# Controller.net
KiCad netlist of a schematic drawn in EAGLE
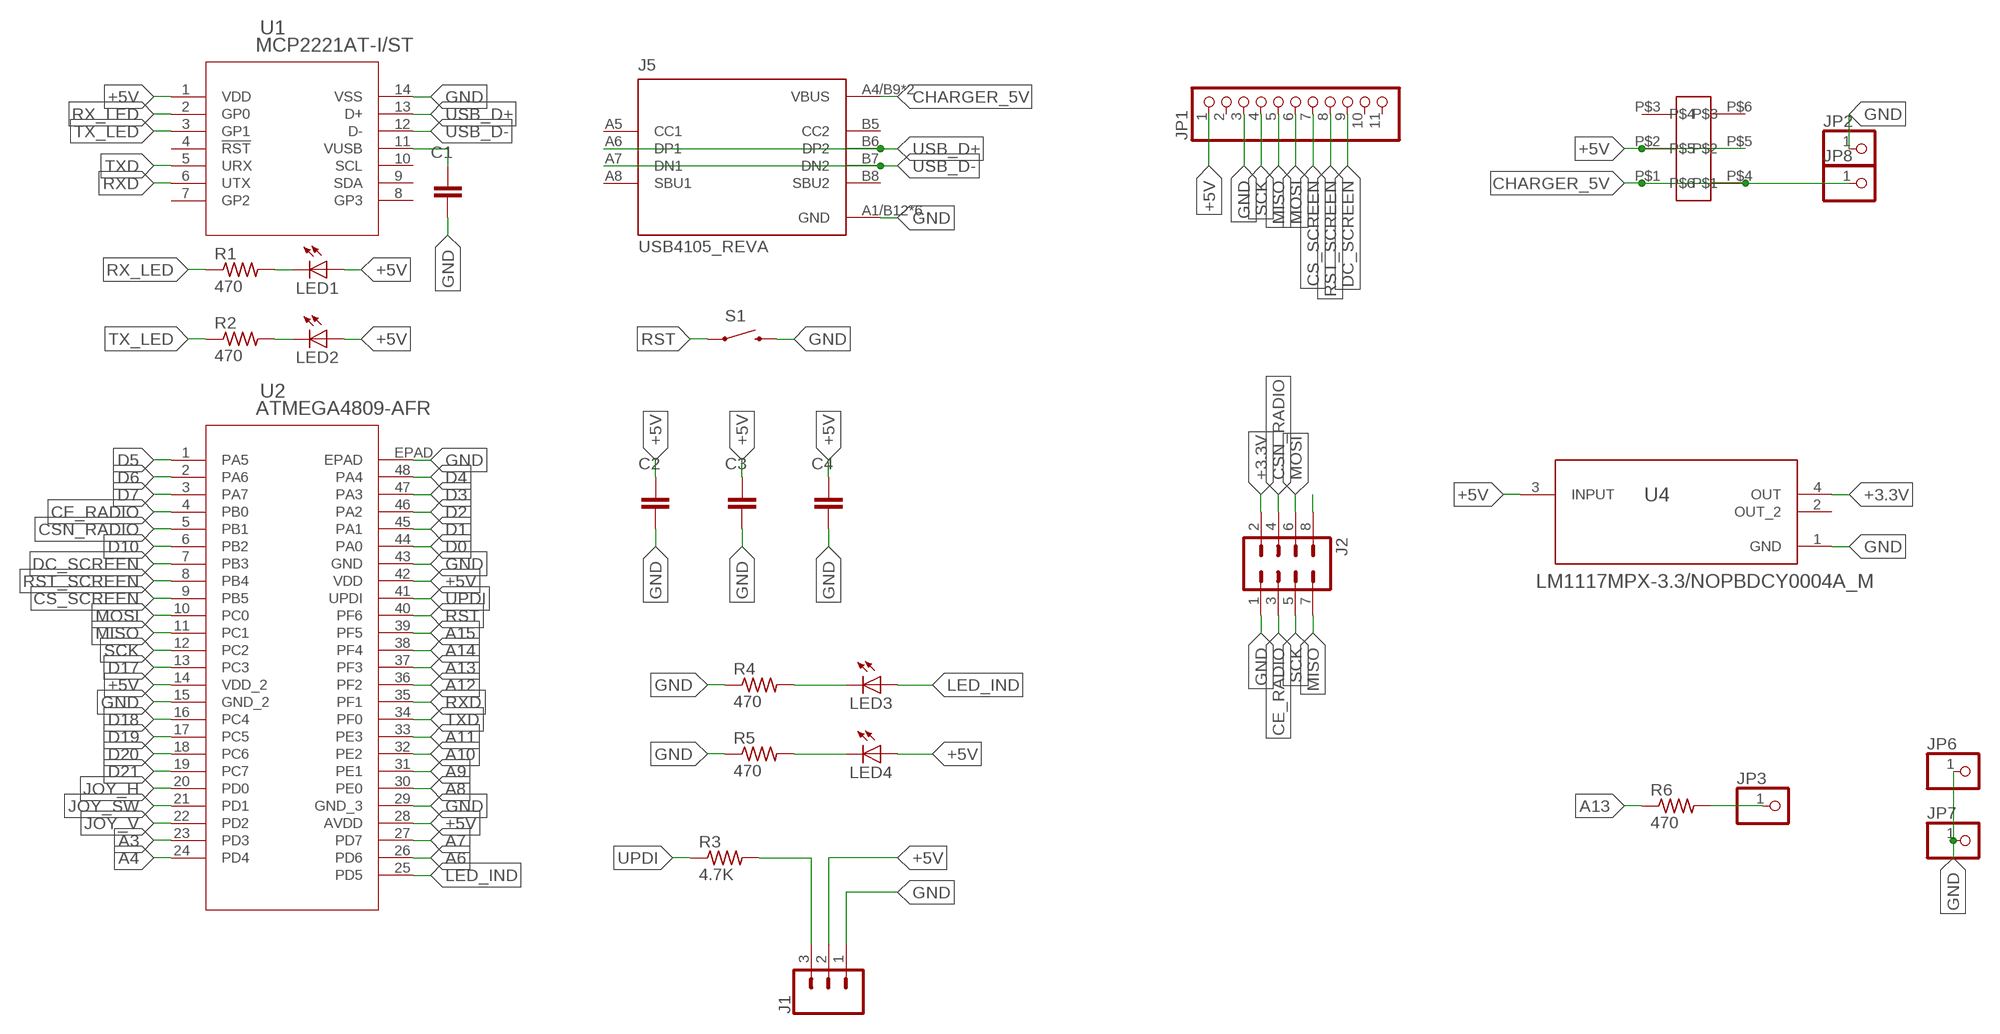
[diagram p0: schematic, sheet 1]

(export (version "E")
  (design (tool "Eeschema 10.0.6"))
  (components
    (comp (ref "C1")
      (value "0.22uF")
      (footprint "eagle-import:CAP_0805")
      (fields
        (field (name "DIGIKEY_PART_NUMBER") "311-1140-2-ND")
        (field (name "MANUFACTURER") "Yageo")
        (field (name "MPN") "CC0805KRX7R9BB104")
        (field (name "CREATED_BY") "PCBLayout.com")
      )
      (libsource (lib "eagle-import") (part "CC0805KRX7R9BB104"))
    )
    (comp (ref "C2")
      (value "0.1uF")
      (footprint "eagle-import:CAP_0805")
      (fields
        (field (name "DIGIKEY_PART_NUMBER") "311-1140-2-ND")
        (field (name "MANUFACTURER") "Yageo")
        (field (name "MPN") "CC0805KRX7R9BB104")
        (field (name "CREATED_BY") "PCBLayout.com")
      )
      (libsource (lib "eagle-import") (part "CC0805KRX7R9BB104"))
    )
    (comp (ref "C3")
      (value "0.1uF")
      (footprint "eagle-import:CAP_0805")
      (fields
        (field (name "DIGIKEY_PART_NUMBER") "311-1140-2-ND")
        (field (name "MANUFACTURER") "Yageo")
        (field (name "MPN") "CC0805KRX7R9BB104")
        (field (name "CREATED_BY") "PCBLayout.com")
      )
      (libsource (lib "eagle-import") (part "CC0805KRX7R9BB104"))
    )
    (comp (ref "C4")
      (value "0.1uF")
      (footprint "eagle-import:CAP_0805")
      (fields
        (field (name "DIGIKEY_PART_NUMBER") "311-1140-2-ND")
        (field (name "MANUFACTURER") "Yageo")
        (field (name "MPN") "CC0805KRX7R9BB104")
        (field (name "CREATED_BY") "PCBLayout.com")
      )
      (libsource (lib "eagle-import") (part "CC0805KRX7R9BB104"))
    )
    (comp (ref "J1")
      (value "CONN_03SMD_RA_MALE")
      (footprint "eagle-import:1X03_SMD_RA_MALE")
      (libsource (lib "eagle-import") (part "CONN_03SMD_RA_MALE"))
    )
    (comp (ref "J2")
      (value "MA04-2")
      (footprint "eagle-import:MA04-2")
      (libsource (lib "eagle-import") (part "MA04-2"))
    )
    (comp (ref "J5")
      (value "USB4105_REVA")
      (footprint "eagle-import:GCT_USB4105_REVA")
      (fields (field (name "MF") "Global Connector Technology") (field (name "MP") "USB4105"))
      (libsource (lib "eagle-import") (part "USB4105_REVA"))
    )
    (comp (ref "JP1")
      (value "PINHD-1X11")
      (footprint "eagle-import:1X11")
      (libsource (lib "eagle-import") (part "PINHD-1X11"))
    )
    (comp (ref "JP2")
      (value "PINHD-1X1")
      (footprint "eagle-import:1X01")
      (libsource (lib "eagle-import") (part "PINHD-1X1"))
    )
    (comp (ref "JP3")
      (value "PINHD-1X1")
      (footprint "eagle-import:1X01")
      (libsource (lib "eagle-import") (part "PINHD-1X1"))
    )
    (comp (ref "JP6")
      (value "PINHD-1X1")
      (footprint "eagle-import:1X01")
      (libsource (lib "eagle-import") (part "PINHD-1X1"))
    )
    (comp (ref "JP7")
      (value "PINHD-1X1")
      (footprint "eagle-import:1X01")
      (libsource (lib "eagle-import") (part "PINHD-1X1"))
    )
    (comp (ref "JP8")
      (value "PINHD-1X1")
      (footprint "eagle-import:1X01")
      (libsource (lib "eagle-import") (part "PINHD-1X1"))
    )
    (comp (ref "LED1")
      (value "LEDCHIPLED_0805")
      (footprint "eagle-import:CHIPLED_0805")
      (libsource (lib "eagle-import") (part "LEDCHIPLED_0805"))
    )
    (comp (ref "LED2")
      (value "LEDCHIPLED_0805")
      (footprint "eagle-import:CHIPLED_0805")
      (libsource (lib "eagle-import") (part "LEDCHIPLED_0805"))
    )
    (comp (ref "LED3")
      (value "LEDCHIPLED_0805")
      (footprint "eagle-import:CHIPLED_0805")
      (libsource (lib "eagle-import") (part "LEDCHIPLED_0805"))
    )
    (comp (ref "LED4")
      (value "LEDCHIPLED_0805")
      (footprint "eagle-import:CHIPLED_0805")
      (libsource (lib "eagle-import") (part "LEDCHIPLED_0805"))
    )
    (comp (ref "R1")
      (value "470")
      (footprint "eagle-import:R0805")
      (libsource (lib "eagle-import") (part "R-US_R0805"))
    )
    (comp (ref "R2")
      (value "470")
      (footprint "eagle-import:R0805")
      (libsource (lib "eagle-import") (part "R-US_R0805"))
    )
    (comp (ref "R3")
      (value "4.7K")
      (footprint "eagle-import:R0805")
      (libsource (lib "eagle-import") (part "R-US_R0805"))
    )
    (comp (ref "R4")
      (value "470")
      (footprint "eagle-import:R0805")
      (libsource (lib "eagle-import") (part "R-US_R0805"))
    )
    (comp (ref "R5")
      (value "470")
      (footprint "eagle-import:R0805")
      (libsource (lib "eagle-import") (part "R-US_R0805"))
    )
    (comp (ref "R6")
      (value "470")
      (footprint "eagle-import:R0805")
      (libsource (lib "eagle-import") (part "R-US_R0805"))
    )
    (comp (ref "S1")
      (value "RS032G05A3SM-SPST-MOMENTARY-SWSMD-1101NE")
      (footprint "eagle-import:TACTILE-SWITCH-1101NE")
      (libsource (lib "eagle-import") (part "RS032G05A3SM-SPST-MOMENTARY-SWSMD-1101NE"))
    )
    (comp (ref "U$47")
      (value "JS202011JAQN")
      (footprint "eagle-import:JS202011JAQN")
      (libsource (lib "eagle-import") (part "JS202011JAQN"))
    )
    (comp (ref "U1")
      (value "MCP2221AT-I/ST")
      (footprint "eagle-import:TSSOP14_ST_MCH")
      (fields (field (name "COPYRIGHT") "Copyright (C) 2018 Accelerated Designs. All rights reserved"))
      (libsource (lib "eagle-import") (part "MCP2221AT-I/ST"))
    )
    (comp (ref "U2")
      (value "ATMEGA4809-AFR")
      (footprint "eagle-import:TQFP48_7X7MC_MCH")
      (fields (field (name "COPYRIGHT") "Copyright (C) 2018 Accelerated Designs. All rights reserved"))
      (libsource (lib "eagle-import") (part "ATMEGA4809-AFR"))
    )
    (comp (ref "U4")
      (value "LM1117MPX-3.3/NOPBDCY0004A_M")
      (footprint "eagle-import:DCY0004A_M")
      (fields
        (field (name "MANUFACTURER_PART_NUMBER") "LM1117MPX-3.3/NOPB")
        (field (name "COPYRIGHT") "Copyright (C) 2022 Ultra Librarian. All rights reserved.")
      )
      (libsource (lib "eagle-import") (part "LM1117MPX-3.3/NOPBDCY0004A_M"))
    )
  )
  (nets
    (net (code "1") (name "+3.3V") (class "Default")
      (node (ref "J2") (pin "2") (pinfunction "2_2") (pintype "passive"))
      (node (ref "U4") (pin "4") (pinfunction "OUT_4") (pintype "power_in"))
    )
    (net (code "2") (name "+5V") (class "Default")
      (node (ref "C2") (pin "1") (pinfunction "1_1") (pintype "passive"))
      (node (ref "C3") (pin "1") (pinfunction "1_1") (pintype "passive"))
      (node (ref "C4") (pin "1") (pinfunction "1_1") (pintype "passive"))
      (node (ref "J1") (pin "2") (pinfunction "2_2") (pintype "passive"))
      (node (ref "JP1") (pin "1") (pinfunction "1_1") (pintype "passive"))
      (node (ref "LED1") (pin "A") (pinfunction "A_A") (pintype "passive"))
      (node (ref "LED2") (pin "A") (pinfunction "A_A") (pintype "passive"))
      (node (ref "LED4") (pin "A") (pinfunction "A_A") (pintype "passive"))
      (node (ref "U$47") (pin "P$2") (pinfunction "P$2_P$2") (pintype "bidirectional"))
      (node (ref "U$47") (pin "P$5") (pinfunction "P$5_P$5") (pintype "bidirectional"))
      (node (ref "U1") (pin "1") (pinfunction "VDD_1") (pintype "power_in"))
      (node (ref "U2") (pin "14") (pinfunction "VDD_2_14") (pintype "power_in"))
      (node (ref "U2") (pin "28") (pinfunction "AVDD_28") (pintype "power_in"))
      (node (ref "U2") (pin "42") (pinfunction "VDD_42") (pintype "power_in"))
      (node (ref "U4") (pin "3") (pinfunction "INPUT_3") (pintype "power_in"))
    )
    (net (code "3") (name "/OUT_2") (class "Default")
      (node (ref "U4") (pin "2") (pinfunction "OUT_2_2") (pintype "power_in"))
    )
    (net (code "4") (name "A3") (class "Default")
      (node (ref "U2") (pin "23") (pinfunction "PD3_23") (pintype "bidirectional"))
    )
    (net (code "5") (name "A4") (class "Default")
      (node (ref "U2") (pin "24") (pinfunction "PD4_24") (pintype "bidirectional"))
    )
    (net (code "6") (name "A6") (class "Default")
      (node (ref "U2") (pin "26") (pinfunction "PD6_26") (pintype "bidirectional"))
    )
    (net (code "7") (name "A7") (class "Default")
      (node (ref "U2") (pin "27") (pinfunction "PD7_27") (pintype "bidirectional"))
    )
    (net (code "8") (name "A8") (class "Default")
      (node (ref "U2") (pin "30") (pinfunction "PE0_30") (pintype "bidirectional"))
    )
    (net (code "9") (name "A9") (class "Default")
      (node (ref "U2") (pin "31") (pinfunction "PE1_31") (pintype "bidirectional"))
    )
    (net (code "10") (name "A10") (class "Default")
      (node (ref "U2") (pin "32") (pinfunction "PE2_32") (pintype "bidirectional"))
    )
    (net (code "11") (name "A11") (class "Default")
      (node (ref "U2") (pin "33") (pinfunction "PE3_33") (pintype "bidirectional"))
    )
    (net (code "12") (name "A12") (class "Default")
      (node (ref "U2") (pin "36") (pinfunction "PF2_36") (pintype "bidirectional"))
    )
    (net (code "13") (name "A13") (class "Default")
      (node (ref "R6") (pin "1") (pinfunction "1_1") (pintype "passive"))
      (node (ref "U2") (pin "37") (pinfunction "PF3_37") (pintype "bidirectional"))
    )
    (net (code "14") (name "A14") (class "Default")
      (node (ref "U2") (pin "38") (pinfunction "PF4_38") (pintype "bidirectional"))
    )
    (net (code "15") (name "A15") (class "Default")
      (node (ref "U2") (pin "39") (pinfunction "PF5_39") (pintype "bidirectional"))
    )
    (net (code "16") (name "CE_RADIO") (class "Default")
      (node (ref "J2") (pin "3") (pinfunction "3_3") (pintype "passive"))
      (node (ref "U2") (pin "4") (pinfunction "PB0_4") (pintype "bidirectional"))
    )
    (net (code "17") (name "CHARGER_5V") (class "Default")
      (node (ref "J5") (pin "A4/B9") (pinfunction "VBUS_A4/B9") (pintype "power_in"))
      (node (ref "J5") (pin "B4/A9") (pinfunction "VBUS_B4/A9") (pintype "power_in"))
      (node (ref "JP8") (pin "1") (pinfunction "1_1") (pintype "passive"))
      (node (ref "U$47") (pin "P$1") (pinfunction "P$1_P$1") (pintype "bidirectional"))
      (node (ref "U$47") (pin "P$4") (pinfunction "P$6_P$4") (pintype "bidirectional"))
    )
    (net (code "18") (name "CSN_RADIO") (class "Default")
      (node (ref "J2") (pin "4") (pinfunction "4_4") (pintype "passive"))
      (node (ref "U2") (pin "5") (pinfunction "PB1_5") (pintype "bidirectional"))
    )
    (net (code "19") (name "CS_SCREEN") (class "Default")
      (node (ref "JP1") (pin "7") (pinfunction "7_7") (pintype "passive"))
      (node (ref "U2") (pin "9") (pinfunction "PB5_9") (pintype "bidirectional"))
    )
    (net (code "20") (name "D0") (class "Default")
      (node (ref "U2") (pin "44") (pinfunction "PA0_44") (pintype "bidirectional"))
    )
    (net (code "21") (name "D1") (class "Default")
      (node (ref "U2") (pin "45") (pinfunction "PA1_45") (pintype "bidirectional"))
    )
    (net (code "22") (name "D2") (class "Default")
      (node (ref "U2") (pin "46") (pinfunction "PA2_46") (pintype "bidirectional"))
    )
    (net (code "23") (name "D3") (class "Default")
      (node (ref "U2") (pin "47") (pinfunction "PA3_47") (pintype "bidirectional"))
    )
    (net (code "24") (name "D4") (class "Default")
      (node (ref "U2") (pin "48") (pinfunction "PA4_48") (pintype "bidirectional"))
    )
    (net (code "25") (name "D5") (class "Default")
      (node (ref "U2") (pin "1") (pinfunction "PA5_1") (pintype "bidirectional"))
    )
    (net (code "26") (name "D6") (class "Default")
      (node (ref "U2") (pin "2") (pinfunction "PA6_2") (pintype "bidirectional"))
    )
    (net (code "27") (name "D7") (class "Default")
      (node (ref "U2") (pin "3") (pinfunction "PA7_3") (pintype "bidirectional"))
    )
    (net (code "28") (name "D10") (class "Default")
      (node (ref "U2") (pin "6") (pinfunction "PB2_6") (pintype "bidirectional"))
    )
    (net (code "29") (name "D17") (class "Default")
      (node (ref "U2") (pin "13") (pinfunction "PC3_13") (pintype "bidirectional"))
    )
    (net (code "30") (name "D18") (class "Default")
      (node (ref "U2") (pin "16") (pinfunction "PC4_16") (pintype "bidirectional"))
    )
    (net (code "31") (name "D19") (class "Default")
      (node (ref "U2") (pin "17") (pinfunction "PC5_17") (pintype "bidirectional"))
    )
    (net (code "32") (name "D20") (class "Default")
      (node (ref "U2") (pin "18") (pinfunction "PC6_18") (pintype "bidirectional"))
    )
    (net (code "33") (name "D21") (class "Default")
      (node (ref "U2") (pin "19") (pinfunction "PC7_19") (pintype "bidirectional"))
    )
    (net (code "34") (name "DC_SCREEN") (class "Default")
      (node (ref "JP1") (pin "9") (pinfunction "9_9") (pintype "passive"))
      (node (ref "U2") (pin "7") (pinfunction "PB3_7") (pintype "bidirectional"))
    )
    (net (code "35") (name "GND") (class "Default")
      (node (ref "C1") (pin "2") (pinfunction "2_2") (pintype "passive"))
      (node (ref "C2") (pin "2") (pinfunction "2_2") (pintype "passive"))
      (node (ref "C3") (pin "2") (pinfunction "2_2") (pintype "passive"))
      (node (ref "C4") (pin "2") (pinfunction "2_2") (pintype "passive"))
      (node (ref "J1") (pin "1") (pinfunction "1_1") (pintype "passive"))
      (node (ref "J2") (pin "1") (pinfunction "1_1") (pintype "passive"))
      (node (ref "J5") (pin "A1/B12") (pinfunction "GND_A1/B12") (pintype "power_in"))
      (node (ref "J5") (pin "B1/A12") (pinfunction "GND_B1/A12") (pintype "power_in"))
      (node (ref "J5") (pin "G1") (pinfunction "GND_G1") (pintype "power_in"))
      (node (ref "J5") (pin "G2") (pinfunction "GND_G2") (pintype "power_in"))
      (node (ref "J5") (pin "G3") (pinfunction "GND_G3") (pintype "power_in"))
      (node (ref "J5") (pin "G4") (pinfunction "GND_G4") (pintype "power_in"))
      (node (ref "JP1") (pin "3") (pinfunction "3_3") (pintype "passive"))
      (node (ref "JP2") (pin "1") (pinfunction "1_1") (pintype "passive"))
      (node (ref "JP6") (pin "1") (pinfunction "1_1") (pintype "passive"))
      (node (ref "JP7") (pin "1") (pinfunction "1_1") (pintype "passive"))
      (node (ref "R4") (pin "1") (pinfunction "1_1") (pintype "passive"))
      (node (ref "R5") (pin "1") (pinfunction "1_1") (pintype "passive"))
      (node (ref "S1") (pin "2") (pinfunction "2_2") (pintype "passive"))
      (node (ref "U1") (pin "14") (pinfunction "VSS_14") (pintype "passive"))
      (node (ref "U2") (pin "15") (pinfunction "GND_2_15") (pintype "power_in"))
      (node (ref "U2") (pin "29") (pinfunction "GND_3_29") (pintype "power_in"))
      (node (ref "U2") (pin "43") (pinfunction "GND_43") (pintype "power_in"))
      (node (ref "U2") (pin "EPAD") (pinfunction "EPAD_EPAD") (pintype "passive"))
      (node (ref "U4") (pin "1") (pinfunction "GND_1") (pintype "power_in"))
    )
    (net (code "36") (name "JOY_H") (class "Default")
      (node (ref "U2") (pin "20") (pinfunction "PD0_20") (pintype "bidirectional"))
    )
    (net (code "37") (name "JOY_SW") (class "Default")
      (node (ref "U2") (pin "21") (pinfunction "PD1_21") (pintype "bidirectional"))
    )
    (net (code "38") (name "JOY_V") (class "Default")
      (node (ref "U2") (pin "22") (pinfunction "PD2_22") (pintype "bidirectional"))
    )
    (net (code "39") (name "LED_IND") (class "Default")
      (node (ref "LED3") (pin "A") (pinfunction "A_A") (pintype "passive"))
      (node (ref "U2") (pin "25") (pinfunction "PD5_25") (pintype "bidirectional"))
    )
    (net (code "40") (name "MISO") (class "Default")
      (node (ref "J2") (pin "7") (pinfunction "7_7") (pintype "passive"))
      (node (ref "JP1") (pin "5") (pinfunction "5_5") (pintype "passive"))
      (node (ref "U2") (pin "11") (pinfunction "PC1_11") (pintype "bidirectional"))
    )
    (net (code "41") (name "MOSI") (class "Default")
      (node (ref "J2") (pin "6") (pinfunction "6_6") (pintype "passive"))
      (node (ref "JP1") (pin "6") (pinfunction "6_6") (pintype "passive"))
      (node (ref "U2") (pin "10") (pinfunction "PC0_10") (pintype "bidirectional"))
    )
    (net (code "42") (name "Net-(J1-Pad3)") (class "Default")
      (node (ref "J1") (pin "3") (pinfunction "3_3") (pintype "passive"))
      (node (ref "R3") (pin "2") (pinfunction "2_2") (pintype "passive"))
    )
    (net (code "43") (name "Net-(JP3-Pad1)") (class "Default")
      (node (ref "JP3") (pin "1") (pinfunction "1_1") (pintype "passive"))
      (node (ref "R6") (pin "2") (pinfunction "2_2") (pintype "passive"))
    )
    (net (code "44") (name "Net-(LED1-PadC)") (class "Default")
      (node (ref "LED1") (pin "C") (pinfunction "C_C") (pintype "passive"))
      (node (ref "R1") (pin "2") (pinfunction "2_2") (pintype "passive"))
    )
    (net (code "45") (name "Net-(LED2-PadC)") (class "Default")
      (node (ref "LED2") (pin "C") (pinfunction "C_C") (pintype "passive"))
      (node (ref "R2") (pin "2") (pinfunction "2_2") (pintype "passive"))
    )
    (net (code "46") (name "Net-(LED3-PadC)") (class "Default")
      (node (ref "LED3") (pin "C") (pinfunction "C_C") (pintype "passive"))
      (node (ref "R4") (pin "2") (pinfunction "2_2") (pintype "passive"))
    )
    (net (code "47") (name "Net-(LED4-PadC)") (class "Default")
      (node (ref "LED4") (pin "C") (pinfunction "C_C") (pintype "passive"))
      (node (ref "R5") (pin "2") (pinfunction "2_2") (pintype "passive"))
    )
    (net (code "48") (name "Net-(U1-VUSB)") (class "Default")
      (node (ref "C1") (pin "1") (pinfunction "1_1") (pintype "passive"))
      (node (ref "U1") (pin "11") (pinfunction "VUSB_11") (pintype "power_in"))
    )
    (net (code "49") (name "RST") (class "Default")
      (node (ref "S1") (pin "1") (pinfunction "1_1") (pintype "passive"))
      (node (ref "U2") (pin "40") (pinfunction "PF6_40") (pintype "bidirectional"))
    )
    (net (code "50") (name "RST_SCREEN") (class "Default")
      (node (ref "JP1") (pin "8") (pinfunction "8_8") (pintype "passive"))
      (node (ref "U2") (pin "8") (pinfunction "PB4_8") (pintype "bidirectional"))
    )
    (net (code "51") (name "RXD") (class "Default")
      (node (ref "U1") (pin "6") (pinfunction "UTX_6") (pintype "output"))
      (node (ref "U2") (pin "35") (pinfunction "PF1_35") (pintype "bidirectional"))
    )
    (net (code "52") (name "RX_LED") (class "Default")
      (node (ref "R1") (pin "1") (pinfunction "1_1") (pintype "passive"))
      (node (ref "U1") (pin "2") (pinfunction "GP0_2") (pintype "bidirectional"))
    )
    (net (code "53") (name "SCK") (class "Default")
      (node (ref "J2") (pin "5") (pinfunction "5_5") (pintype "passive"))
      (node (ref "JP1") (pin "4") (pinfunction "4_4") (pintype "passive"))
      (node (ref "U2") (pin "12") (pinfunction "PC2_12") (pintype "bidirectional"))
    )
    (net (code "54") (name "TXD") (class "Default")
      (node (ref "U1") (pin "5") (pinfunction "URX_5") (pintype "input"))
      (node (ref "U2") (pin "34") (pinfunction "PF0_34") (pintype "bidirectional"))
    )
    (net (code "55") (name "TX_LED") (class "Default")
      (node (ref "R2") (pin "1") (pinfunction "1_1") (pintype "passive"))
      (node (ref "U1") (pin "3") (pinfunction "GP1_3") (pintype "bidirectional"))
    )
    (net (code "56") (name "UPDI") (class "Default")
      (node (ref "R3") (pin "1") (pinfunction "1_1") (pintype "passive"))
      (node (ref "U2") (pin "41") (pinfunction "UPDI_41") (pintype "bidirectional"))
    )
    (net (code "57") (name "USB_D+") (class "Default")
      (node (ref "J5") (pin "A6") (pinfunction "DP1_A6") (pintype "bidirectional"))
      (node (ref "J5") (pin "B6") (pinfunction "DP2_B6") (pintype "bidirectional"))
      (node (ref "U1") (pin "13") (pinfunction "D+_13") (pintype "bidirectional"))
    )
    (net (code "58") (name "USB_D-") (class "Default")
      (node (ref "J5") (pin "A7") (pinfunction "DN1_A7") (pintype "bidirectional"))
      (node (ref "J5") (pin "B7") (pinfunction "DN2_B7") (pintype "bidirectional"))
      (node (ref "U1") (pin "12") (pinfunction "D-_12") (pintype "bidirectional"))
    )
    (net (code "59") (name "unconnected-(J2-Pad8)") (class "Default")
      (node (ref "J2") (pin "8") (pinfunction "8_8") (pintype "passive"))
    )
    (net (code "60") (name "unconnected-(J5-CC1-PadA5)") (class "Default")
      (node (ref "J5") (pin "A5") (pinfunction "CC1_A5") (pintype "bidirectional"))
    )
    (net (code "61") (name "unconnected-(J5-CC2-PadB5)") (class "Default")
      (node (ref "J5") (pin "B5") (pinfunction "CC2_B5") (pintype "bidirectional"))
    )
    (net (code "62") (name "unconnected-(J5-SBU1-PadA8)") (class "Default")
      (node (ref "J5") (pin "A8") (pinfunction "SBU1_A8") (pintype "bidirectional"))
    )
    (net (code "63") (name "unconnected-(J5-SBU2-PadB8)") (class "Default")
      (node (ref "J5") (pin "B8") (pinfunction "SBU2_B8") (pintype "bidirectional"))
    )
    (net (code "64") (name "unconnected-(JP1-Pad2)") (class "Default")
      (node (ref "JP1") (pin "2") (pinfunction "2_2") (pintype "passive"))
    )
    (net (code "65") (name "unconnected-(JP1-Pad10)") (class "Default")
      (node (ref "JP1") (pin "10") (pinfunction "10_10") (pintype "passive"))
    )
    (net (code "66") (name "unconnected-(JP1-Pad11)") (class "Default")
      (node (ref "JP1") (pin "11") (pinfunction "11_11") (pintype "passive"))
    )
    (net (code "67") (name "unconnected-(U$47-P$4-PadP$6)") (class "Default")
      (node (ref "U$47") (pin "P$6") (pinfunction "P$4_P$6") (pintype "bidirectional"))
    )
    (net (code "68") (name "unconnected-(U$47-PadP$3)") (class "Default")
      (node (ref "U$47") (pin "P$3") (pinfunction "P$3_P$3") (pintype "bidirectional"))
    )
    (net (code "69") (name "unconnected-(U1-GP2-Pad7)") (class "Default")
      (node (ref "U1") (pin "7") (pinfunction "GP2_7") (pintype "bidirectional"))
    )
    (net (code "70") (name "unconnected-(U1-GP3-Pad8)") (class "Default")
      (node (ref "U1") (pin "8") (pinfunction "GP3_8") (pintype "bidirectional"))
    )
    (net (code "71") (name "unconnected-(U1-SCL-Pad10)") (class "Default")
      (node (ref "U1") (pin "10") (pinfunction "SCL_10") (pintype "bidirectional"))
    )
    (net (code "72") (name "unconnected-(U1-SDA-Pad9)") (class "Default")
      (node (ref "U1") (pin "9") (pinfunction "SDA_9") (pintype "bidirectional"))
    )
    (net (code "73") (name "unconnected-(U1-~{RST}-Pad4)") (class "Default")
      (node (ref "U1") (pin "4") (pinfunction "~{RST}_4") (pintype "input"))
    )
  )
)
